# 8085-lock-schematic.net
KiCad netlist of a schematic drawn in EAGLE
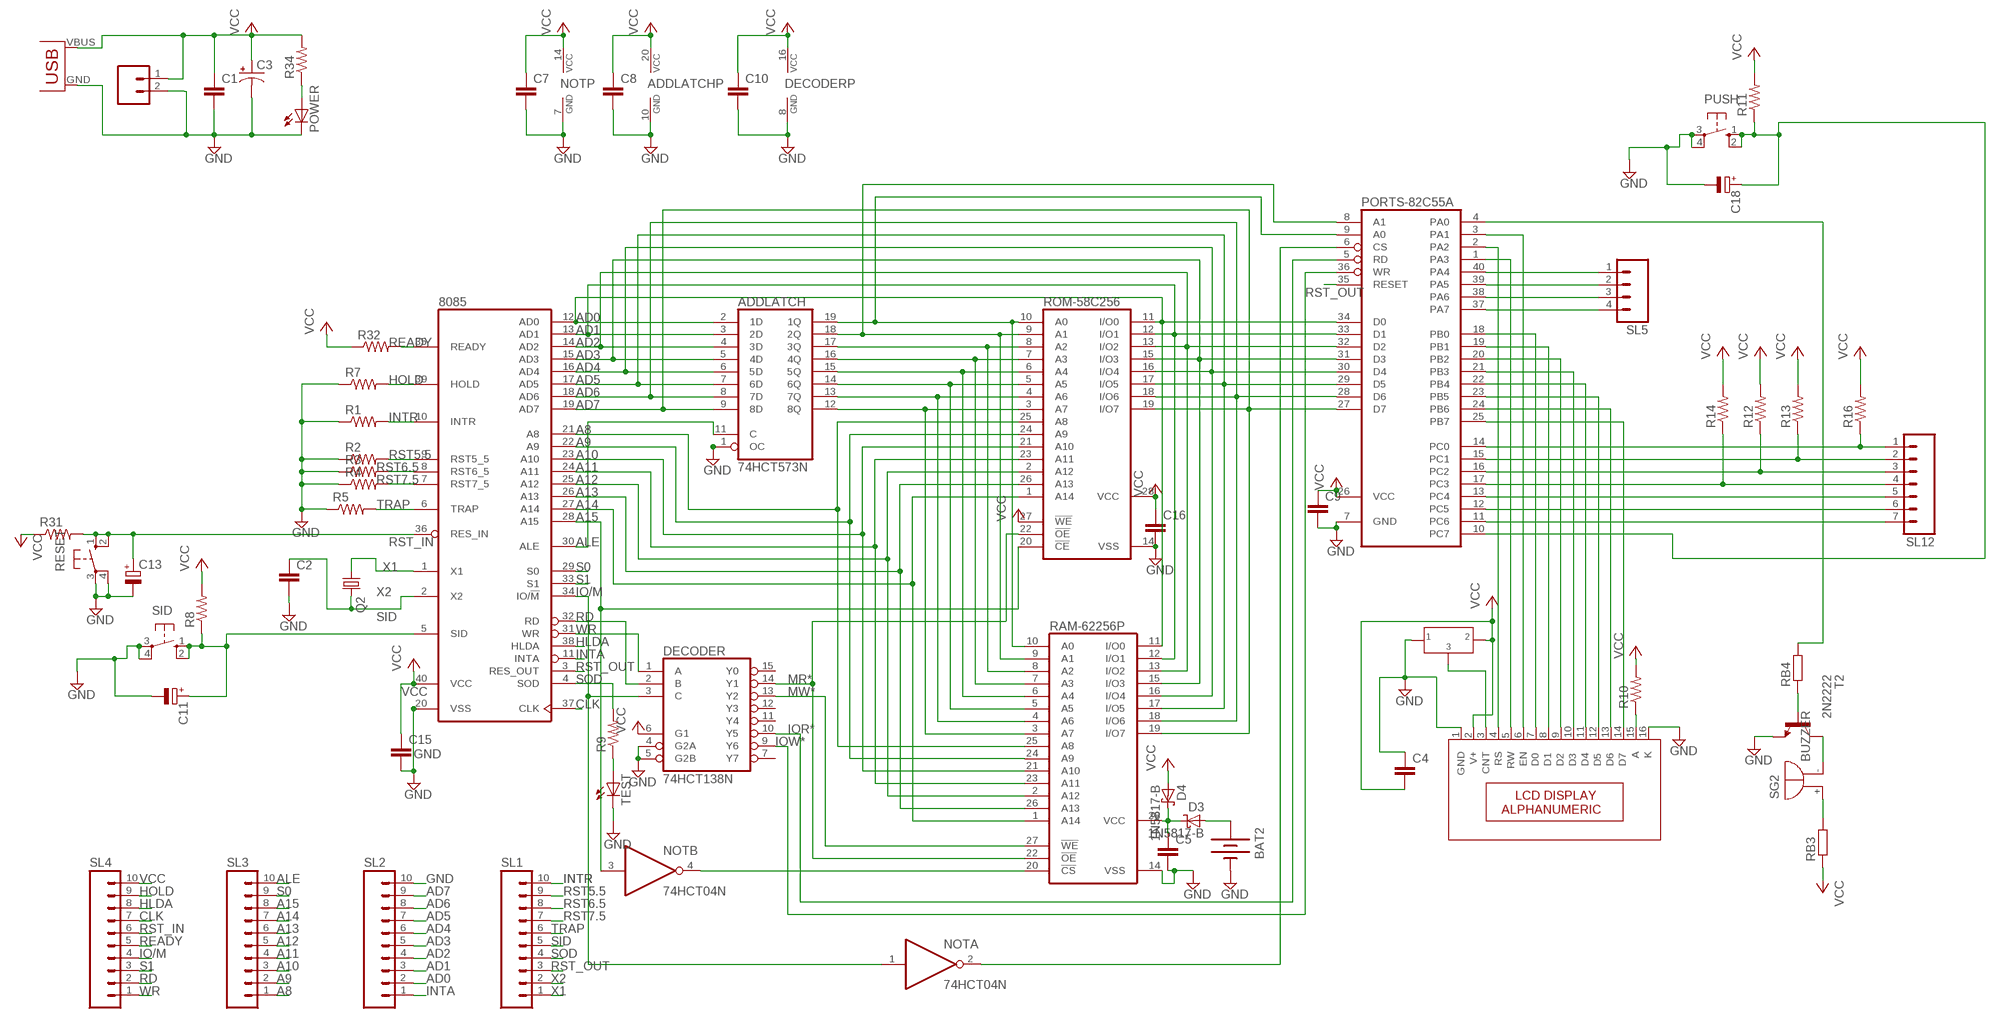
[diagram p0: schematic, sheet 1]

(export (version "E")
  (design (tool "Eeschema 10.0.6"))
  (components
    (comp (ref "8085")
      (value "8085")
      (footprint "eagle-import:DIL40")
      (libsource (lib "eagle-import") (part "8085"))
    )
    (comp (ref "ADDLATCH")
      (value "74HCT573N")
      (footprint "eagle-import:DIL20")
      (libsource (lib "eagle-import") (part "74573NHCT"))
    )
    (comp (ref "BAT2")
      (value "BATTERY20PTH")
      (footprint "eagle-import:BATTCOM_20MM_PTH")
      (libsource (lib "eagle-import") (part "BATTERY20PTH"))
    )
    (comp (ref "C1")
      (value "C-EU025-024X044")
      (footprint "eagle-import:C025-024X044")
      (libsource (lib "eagle-import") (part "C-EU025-024X044"))
    )
    (comp (ref "C2")
      (value "C-EU025-024X044")
      (footprint "eagle-import:C025-024X044")
      (libsource (lib "eagle-import") (part "C-EU025-024X044"))
    )
    (comp (ref "C3")
      (value "CPOL-USE2.5-5")
      (footprint "eagle-import:E2,5-5")
      (libsource (lib "eagle-import") (part "CPOL-USE2.5-5"))
    )
    (comp (ref "C4")
      (value "C-EU025-024X044")
      (footprint "eagle-import:C025-024X044")
      (libsource (lib "eagle-import") (part "C-EU025-024X044"))
    )
    (comp (ref "C5")
      (value "C-EU025-024X044")
      (footprint "eagle-import:C025-024X044")
      (libsource (lib "eagle-import") (part "C-EU025-024X044"))
    )
    (comp (ref "C7")
      (value "C-EU025-024X044")
      (footprint "eagle-import:C025-024X044")
      (libsource (lib "eagle-import") (part "C-EU025-024X044"))
    )
    (comp (ref "C8")
      (value "C-EU025-024X044")
      (footprint "eagle-import:C025-024X044")
      (libsource (lib "eagle-import") (part "C-EU025-024X044"))
    )
    (comp (ref "C9")
      (value "C-EU025-024X044")
      (footprint "eagle-import:C025-024X044")
      (libsource (lib "eagle-import") (part "C-EU025-024X044"))
    )
    (comp (ref "C10")
      (value "C-EU025-024X044")
      (footprint "eagle-import:C025-024X044")
      (libsource (lib "eagle-import") (part "C-EU025-024X044"))
    )
    (comp (ref "C11")
      (value "CPOL-EUE2.5-6")
      (footprint "eagle-import:E2,5-6")
      (libsource (lib "eagle-import") (part "CPOL-EUE2.5-6"))
    )
    (comp (ref "C13")
      (value "CPOL-EUE2.5-6")
      (footprint "eagle-import:E2,5-6")
      (libsource (lib "eagle-import") (part "CPOL-EUE2.5-6"))
    )
    (comp (ref "C15")
      (value "C-EU025-024X044")
      (footprint "eagle-import:C025-024X044")
      (libsource (lib "eagle-import") (part "C-EU025-024X044"))
    )
    (comp (ref "C16")
      (value "C-EU025-024X044")
      (footprint "eagle-import:C025-024X044")
      (libsource (lib "eagle-import") (part "C-EU025-024X044"))
    )
    (comp (ref "C18")
      (value "CPOL-EUE2.5-6")
      (footprint "eagle-import:E2,5-6")
      (libsource (lib "eagle-import") (part "CPOL-EUE2.5-6"))
    )
    (comp (ref "D3")
      (value "1N5817-B")
      (footprint "eagle-import:DO41-7.6")
      (libsource (lib "eagle-import") (part "1N5817-B"))
    )
    (comp (ref "D4")
      (value "1N5817-B")
      (footprint "eagle-import:DO41-7.6")
      (libsource (lib "eagle-import") (part "1N5817-B"))
    )
    (comp (ref "DECODER")
      (value "74HCT138N")
      (footprint "eagle-import:DIL16")
      (libsource (lib "eagle-import") (part "74138NHCT"))
    )
    (comp (ref "NOT")
      (value "74HCT04N")
      (footprint "eagle-import:DIL14")
      (libsource (lib "eagle-import") (part "7404NHCT"))
    )
    (comp (ref "PORTS-82C55A")
      (value "82C55A")
      (footprint "eagle-import:DIL40")
      (fields (field (name "MF") "INTERSIL") (field (name "MPN") "IP82C55AZ"))
      (libsource (lib "eagle-import") (part "82C55A"))
    )
    (comp (ref "POWER")
      (value "LED5MM")
      (footprint "eagle-import:LED5MM")
      (libsource (lib "eagle-import") (part "LED5MM"))
    )
    (comp (ref "PUSH")
      (value "10-XX")
      (footprint "eagle-import:B3F-10XX")
      (libsource (lib "eagle-import") (part "CEDTv79_10-XX"))
    )
    (comp (ref "Q2")
      (value "CRYSTALHC49US")
      (footprint "eagle-import:HC49US")
      (libsource (lib "eagle-import") (part "CRYSTALHC49US"))
    )
    (comp (ref "R1")
      (value "R-US_0207/7")
      (footprint "eagle-import:0207_7")
      (libsource (lib "eagle-import") (part "R-US_0207/7"))
    )
    (comp (ref "R2")
      (value "R-US_0207/7")
      (footprint "eagle-import:0207_7")
      (libsource (lib "eagle-import") (part "R-US_0207/7"))
    )
    (comp (ref "R3")
      (value "R-US_0207/7")
      (footprint "eagle-import:0207_7")
      (libsource (lib "eagle-import") (part "R-US_0207/7"))
    )
    (comp (ref "R4")
      (value "R-US_0207/7")
      (footprint "eagle-import:0207_7")
      (libsource (lib "eagle-import") (part "R-US_0207/7"))
    )
    (comp (ref "R5")
      (value "R-US_0207/7")
      (footprint "eagle-import:0207_7")
      (libsource (lib "eagle-import") (part "R-US_0207/7"))
    )
    (comp (ref "R6")
      (value "PRESET_LR")
      (footprint "eagle-import:PRESET_LR")
      (libsource (lib "eagle-import") (part "PRESET_LR"))
    )
    (comp (ref "R7")
      (value "R-US_0207/7")
      (footprint "eagle-import:0207_7")
      (libsource (lib "eagle-import") (part "R-US_0207/7"))
    )
    (comp (ref "R8")
      (value "R-US_0207/7")
      (footprint "eagle-import:0207_7")
      (libsource (lib "eagle-import") (part "R-US_0207/7"))
    )
    (comp (ref "R9")
      (value "R-US_0207/7")
      (footprint "eagle-import:0207_7")
      (libsource (lib "eagle-import") (part "R-US_0207/7"))
    )
    (comp (ref "R10")
      (value "R-US_0207/7")
      (footprint "eagle-import:0207_7")
      (libsource (lib "eagle-import") (part "R-US_0207/7"))
    )
    (comp (ref "R11")
      (value "R-US_0207/7")
      (footprint "eagle-import:0207_7")
      (libsource (lib "eagle-import") (part "R-US_0207/7"))
    )
    (comp (ref "R12")
      (value "R-US_0207/7")
      (footprint "eagle-import:0207_7")
      (libsource (lib "eagle-import") (part "R-US_0207/7"))
    )
    (comp (ref "R13")
      (value "R-US_0207/7")
      (footprint "eagle-import:0207_7")
      (libsource (lib "eagle-import") (part "R-US_0207/7"))
    )
    (comp (ref "R14")
      (value "R-US_0207/7")
      (footprint "eagle-import:0207_7")
      (libsource (lib "eagle-import") (part "R-US_0207/7"))
    )
    (comp (ref "R16")
      (value "R-US_0207/7")
      (footprint "eagle-import:0207_7")
      (libsource (lib "eagle-import") (part "R-US_0207/7"))
    )
    (comp (ref "R31")
      (value "R-US_0207/7")
      (footprint "eagle-import:0207_7")
      (libsource (lib "eagle-import") (part "R-US_0207/7"))
    )
    (comp (ref "R32")
      (value "R-US_0207/7")
      (footprint "eagle-import:0207_7")
      (libsource (lib "eagle-import") (part "R-US_0207/7"))
    )
    (comp (ref "R34")
      (value "R-US_0207/7")
      (footprint "eagle-import:0207_7")
      (libsource (lib "eagle-import") (part "R-US_0207/7"))
    )
    (comp (ref "RAM-62256P")
      (value "62256P")
      (footprint "eagle-import:DIL28-6")
      (libsource (lib "eagle-import") (part "62256P"))
    )
    (comp (ref "RB3")
      (value "R-EU_0204/7")
      (footprint "eagle-import:0204_7")
      (libsource (lib "eagle-import") (part "R-EU_0204/7"))
    )
    (comp (ref "RB4")
      (value "R-EU_0204/7")
      (footprint "eagle-import:0204_7")
      (libsource (lib "eagle-import") (part "R-EU_0204/7"))
    )
    (comp (ref "RESET")
      (value "10-XX")
      (footprint "eagle-import:B3F-10XX")
      (libsource (lib "eagle-import") (part "10-XX"))
    )
    (comp (ref "ROM-58C256")
      (value "58C256P")
      (footprint "eagle-import:DIL28-6")
      (fields (field (name "MPN") "HN58C256AP85E"))
      (libsource (lib "eagle-import") (part "58C256P"))
    )
    (comp (ref "SG2")
      (value "BUZZER")
      (footprint "eagle-import:F_TMB")
      (libsource (lib "eagle-import") (part "BUZZER"))
    )
    (comp (ref "SID")
      (value "10-XX")
      (footprint "eagle-import:B3F-10XX")
      (libsource (lib "eagle-import") (part "CEDTv79_10-XX"))
    )
    (comp (ref "SL1")
      (value "M10")
      (footprint "eagle-import:10P")
      (libsource (lib "eagle-import") (part "M10"))
    )
    (comp (ref "SL2")
      (value "M10")
      (footprint "eagle-import:10P")
      (libsource (lib "eagle-import") (part "M10"))
    )
    (comp (ref "SL3")
      (value "M10")
      (footprint "eagle-import:10P")
      (libsource (lib "eagle-import") (part "M10"))
    )
    (comp (ref "SL4")
      (value "M10")
      (footprint "eagle-import:10P")
      (libsource (lib "eagle-import") (part "M10"))
    )
    (comp (ref "SL5")
      (value "M04")
      (footprint "eagle-import:04P")
      (libsource (lib "eagle-import") (part "M04"))
    )
    (comp (ref "SL12")
      (value "M07")
      (footprint "eagle-import:07P")
      (libsource (lib "eagle-import") (part "M07"))
    )
    (comp (ref "T2")
      (value "2N2222")
      (footprint "eagle-import:TO18")
      (libsource (lib "eagle-import") (part "2N2222"))
    )
    (comp (ref "TEST")
      (value "LED5MM")
      (footprint "eagle-import:LED5MM")
      (libsource (lib "eagle-import") (part "LED5MM"))
    )
    (comp (ref "U$1")
      (value "M02")
      (footprint "eagle-import:02P")
      (libsource (lib "eagle-import") (part "M02"))
    )
    (comp (ref "U$2")
      (value "USB(POWER)")
      (footprint "eagle-import:USB(POWER)")
      (libsource (lib "eagle-import") (part "USB(POWER)"))
    )
    (comp (ref "U$3")
      (value "LCD-16X2")
      (footprint "eagle-import:16X2-LCD-WITH-MOUNT")
      (libsource (lib "eagle-import") (part "LCD-16X2"))
    )
  )
  (nets
    (net (code "1") (name "/A8") (class "Default")
      (node (ref "8085") (pin "21") (pinfunction "A8_21") (pintype "output"))
      (node (ref "RAM-62256P") (pin "25") (pinfunction "A8_25") (pintype "input"))
      (node (ref "ROM-58C256") (pin "25") (pinfunction "A8_25") (pintype "input"))
      (node (ref "SL3") (pin "1") (pinfunction "1_1") (pintype "passive"))
    )
    (net (code "2") (name "/A9") (class "Default")
      (node (ref "8085") (pin "22") (pinfunction "A9_22") (pintype "output"))
      (node (ref "RAM-62256P") (pin "24") (pinfunction "A9_24") (pintype "input"))
      (node (ref "ROM-58C256") (pin "24") (pinfunction "A9_24") (pintype "input"))
      (node (ref "SL3") (pin "2") (pinfunction "2_2") (pintype "passive"))
    )
    (net (code "3") (name "/A10") (class "Default")
      (node (ref "8085") (pin "23") (pinfunction "A10_23") (pintype "output"))
      (node (ref "RAM-62256P") (pin "21") (pinfunction "A10_21") (pintype "input"))
      (node (ref "ROM-58C256") (pin "21") (pinfunction "A10_21") (pintype "input"))
      (node (ref "SL3") (pin "3") (pinfunction "3_3") (pintype "passive"))
    )
    (net (code "4") (name "/A11") (class "Default")
      (node (ref "8085") (pin "24") (pinfunction "A11_24") (pintype "output"))
      (node (ref "RAM-62256P") (pin "23") (pinfunction "A11_23") (pintype "input"))
      (node (ref "ROM-58C256") (pin "23") (pinfunction "A11_23") (pintype "input"))
      (node (ref "SL3") (pin "4") (pinfunction "4_4") (pintype "passive"))
    )
    (net (code "5") (name "/A12") (class "Default")
      (node (ref "8085") (pin "25") (pinfunction "A12_25") (pintype "output"))
      (node (ref "RAM-62256P") (pin "2") (pinfunction "A12_2") (pintype "input"))
      (node (ref "ROM-58C256") (pin "2") (pinfunction "A12_2") (pintype "input"))
      (node (ref "SL3") (pin "5") (pinfunction "5_5") (pintype "passive"))
    )
    (net (code "6") (name "/A13") (class "Default")
      (node (ref "8085") (pin "26") (pinfunction "A13_26") (pintype "output"))
      (node (ref "RAM-62256P") (pin "26") (pinfunction "A13_26") (pintype "input"))
      (node (ref "ROM-58C256") (pin "26") (pinfunction "A13_26") (pintype "input"))
      (node (ref "SL3") (pin "6") (pinfunction "6_6") (pintype "passive"))
    )
    (net (code "7") (name "/A14") (class "Default")
      (node (ref "8085") (pin "27") (pinfunction "A14_27") (pintype "output"))
      (node (ref "RAM-62256P") (pin "1") (pinfunction "A14_1") (pintype "input"))
      (node (ref "ROM-58C256") (pin "1") (pinfunction "A14_1") (pintype "input"))
      (node (ref "SL3") (pin "7") (pinfunction "7_7") (pintype "passive"))
    )
    (net (code "8") (name "/A15") (class "Default")
      (node (ref "8085") (pin "28") (pinfunction "A15_28") (pintype "output"))
      (node (ref "NOT") (pin "3") (pinfunction "I_3") (pintype "input"))
      (node (ref "ROM-58C256") (pin "20") (pinfunction "~{CE}_20") (pintype "input"))
      (node (ref "SL3") (pin "8") (pinfunction "8_8") (pintype "passive"))
    )
    (net (code "9") (name "/AD0") (class "Default")
      (node (ref "8085") (pin "12") (pinfunction "AD0_12") (pintype "bidirectional"))
      (node (ref "ADDLATCH") (pin "2") (pinfunction "1D_2") (pintype "input"))
      (node (ref "PORTS-82C55A") (pin "34") (pinfunction "D0_34") (pintype "bidirectional"))
      (node (ref "RAM-62256P") (pin "11") (pinfunction "I/O0_11") (pintype "bidirectional"))
      (node (ref "ROM-58C256") (pin "11") (pinfunction "I/O0_11") (pintype "tri_state"))
      (node (ref "SL2") (pin "2") (pinfunction "2_2") (pintype "passive"))
    )
    (net (code "10") (name "/AD1") (class "Default")
      (node (ref "8085") (pin "13") (pinfunction "AD1_13") (pintype "bidirectional"))
      (node (ref "ADDLATCH") (pin "3") (pinfunction "2D_3") (pintype "input"))
      (node (ref "PORTS-82C55A") (pin "33") (pinfunction "D1_33") (pintype "bidirectional"))
      (node (ref "RAM-62256P") (pin "12") (pinfunction "I/O1_12") (pintype "bidirectional"))
      (node (ref "ROM-58C256") (pin "12") (pinfunction "I/O1_12") (pintype "tri_state"))
      (node (ref "SL2") (pin "3") (pinfunction "3_3") (pintype "passive"))
    )
    (net (code "11") (name "/AD2") (class "Default")
      (node (ref "8085") (pin "14") (pinfunction "AD2_14") (pintype "bidirectional"))
      (node (ref "ADDLATCH") (pin "4") (pinfunction "3D_4") (pintype "input"))
      (node (ref "PORTS-82C55A") (pin "32") (pinfunction "D2_32") (pintype "bidirectional"))
      (node (ref "RAM-62256P") (pin "13") (pinfunction "I/O2_13") (pintype "bidirectional"))
      (node (ref "ROM-58C256") (pin "13") (pinfunction "I/O2_13") (pintype "tri_state"))
      (node (ref "SL2") (pin "4") (pinfunction "4_4") (pintype "passive"))
    )
    (net (code "12") (name "/AD3") (class "Default")
      (node (ref "8085") (pin "15") (pinfunction "AD3_15") (pintype "bidirectional"))
      (node (ref "ADDLATCH") (pin "5") (pinfunction "4D_5") (pintype "input"))
      (node (ref "PORTS-82C55A") (pin "31") (pinfunction "D3_31") (pintype "bidirectional"))
      (node (ref "RAM-62256P") (pin "15") (pinfunction "I/O3_15") (pintype "bidirectional"))
      (node (ref "ROM-58C256") (pin "15") (pinfunction "I/O3_15") (pintype "tri_state"))
      (node (ref "SL2") (pin "5") (pinfunction "5_5") (pintype "passive"))
    )
    (net (code "13") (name "/AD4") (class "Default")
      (node (ref "8085") (pin "16") (pinfunction "AD4_16") (pintype "bidirectional"))
      (node (ref "ADDLATCH") (pin "6") (pinfunction "5D_6") (pintype "input"))
      (node (ref "PORTS-82C55A") (pin "30") (pinfunction "D4_30") (pintype "bidirectional"))
      (node (ref "RAM-62256P") (pin "16") (pinfunction "I/O4_16") (pintype "bidirectional"))
      (node (ref "ROM-58C256") (pin "16") (pinfunction "I/O4_16") (pintype "tri_state"))
      (node (ref "SL2") (pin "6") (pinfunction "6_6") (pintype "passive"))
    )
    (net (code "14") (name "/AD5") (class "Default")
      (node (ref "8085") (pin "17") (pinfunction "AD5_17") (pintype "bidirectional"))
      (node (ref "ADDLATCH") (pin "7") (pinfunction "6D_7") (pintype "input"))
      (node (ref "PORTS-82C55A") (pin "29") (pinfunction "D5_29") (pintype "bidirectional"))
      (node (ref "RAM-62256P") (pin "17") (pinfunction "I/O5_17") (pintype "bidirectional"))
      (node (ref "ROM-58C256") (pin "17") (pinfunction "I/O5_17") (pintype "tri_state"))
      (node (ref "SL2") (pin "7") (pinfunction "7_7") (pintype "passive"))
    )
    (net (code "15") (name "/AD6") (class "Default")
      (node (ref "8085") (pin "18") (pinfunction "AD6_18") (pintype "bidirectional"))
      (node (ref "ADDLATCH") (pin "8") (pinfunction "7D_8") (pintype "input"))
      (node (ref "PORTS-82C55A") (pin "28") (pinfunction "D6_28") (pintype "bidirectional"))
      (node (ref "RAM-62256P") (pin "18") (pinfunction "I/O6_18") (pintype "bidirectional"))
      (node (ref "ROM-58C256") (pin "18") (pinfunction "I/O6_18") (pintype "tri_state"))
      (node (ref "SL2") (pin "8") (pinfunction "8_8") (pintype "passive"))
    )
    (net (code "16") (name "/AD7") (class "Default")
      (node (ref "8085") (pin "19") (pinfunction "AD7_19") (pintype "bidirectional"))
      (node (ref "ADDLATCH") (pin "9") (pinfunction "8D_9") (pintype "input"))
      (node (ref "PORTS-82C55A") (pin "27") (pinfunction "D7_27") (pintype "bidirectional"))
      (node (ref "RAM-62256P") (pin "19") (pinfunction "I/O7_19") (pintype "bidirectional"))
      (node (ref "ROM-58C256") (pin "19") (pinfunction "I/O7_19") (pintype "tri_state"))
      (node (ref "SL2") (pin "9") (pinfunction "9_9") (pintype "passive"))
    )
    (net (code "17") (name "/ALE") (class "Default")
      (node (ref "8085") (pin "30") (pinfunction "ALE_30") (pintype "output"))
      (node (ref "ADDLATCH") (pin "11") (pinfunction "C_11") (pintype "input"))
      (node (ref "SL3") (pin "10") (pinfunction "10_10") (pintype "passive"))
    )
    (net (code "18") (name "/CLK") (class "Default")
      (node (ref "8085") (pin "37") (pinfunction "CLK_37") (pintype "output"))
      (node (ref "SL4") (pin "7") (pinfunction "7_7") (pintype "passive"))
    )
    (net (code "19") (name "/HLDA") (class "Default")
      (node (ref "8085") (pin "38") (pinfunction "HLDA_38") (pintype "output"))
      (node (ref "SL4") (pin "8") (pinfunction "8_8") (pintype "passive"))
    )
    (net (code "20") (name "/HOLD") (class "Default")
      (node (ref "8085") (pin "39") (pinfunction "HOLD_39") (pintype "input"))
      (node (ref "R7") (pin "2") (pinfunction "2_2") (pintype "passive"))
      (node (ref "SL4") (pin "9") (pinfunction "9_9") (pintype "passive"))
    )
    (net (code "21") (name "/INTA") (class "Default")
      (node (ref "8085") (pin "11") (pinfunction "INTA_11") (pintype "output"))
      (node (ref "SL2") (pin "1") (pinfunction "1_1") (pintype "passive"))
    )
    (net (code "22") (name "/INTR") (class "Default")
      (node (ref "8085") (pin "10") (pinfunction "INTR_10") (pintype "input"))
      (node (ref "R1") (pin "2") (pinfunction "2_2") (pintype "passive"))
      (node (ref "SL1") (pin "10") (pinfunction "10_10") (pintype "passive"))
    )
    (net (code "23") (name "/IOR*") (class "Default")
      (node (ref "DECODER") (pin "10") (pinfunction "Y5_10") (pintype "output"))
      (node (ref "PORTS-82C55A") (pin "5") (pinfunction "RD_5") (pintype "input"))
    )
    (net (code "24") (name "/IOW*") (class "Default")
      (node (ref "DECODER") (pin "9") (pinfunction "Y6_9") (pintype "output"))
      (node (ref "PORTS-82C55A") (pin "36") (pinfunction "WR_36") (pintype "input"))
    )
    (net (code "25") (name "/IO{slash}M") (class "Default")
      (node (ref "8085") (pin "34") (pinfunction "IO/~{M}_34") (pintype "output"))
      (node (ref "DECODER") (pin "3") (pinfunction "C_3") (pintype "input"))
      (node (ref "NOT") (pin "1") (pinfunction "I_1") (pintype "input"))
      (node (ref "SL4") (pin "4") (pinfunction "4_4") (pintype "passive"))
    )
    (net (code "26") (name "/MR*") (class "Default")
      (node (ref "DECODER") (pin "14") (pinfunction "Y1_14") (pintype "output"))
      (node (ref "RAM-62256P") (pin "22") (pinfunction "~{OE}_22") (pintype "input"))
      (node (ref "ROM-58C256") (pin "22") (pinfunction "~{OE}_22") (pintype "input"))
    )
    (net (code "27") (name "/MW*") (class "Default")
      (node (ref "DECODER") (pin "13") (pinfunction "Y2_13") (pintype "output"))
      (node (ref "RAM-62256P") (pin "27") (pinfunction "~{WE}_27") (pintype "input"))
    )
    (net (code "28") (name "/RD") (class "Default")
      (node (ref "8085") (pin "32") (pinfunction "RD_32") (pintype "output"))
      (node (ref "DECODER") (pin "2") (pinfunction "B_2") (pintype "input"))
      (node (ref "SL4") (pin "2") (pinfunction "2_2") (pintype "passive"))
    )
    (net (code "29") (name "/READY") (class "Default")
      (node (ref "8085") (pin "35") (pinfunction "READY_35") (pintype "input"))
      (node (ref "R32") (pin "2") (pinfunction "2_2") (pintype "passive"))
      (node (ref "SL4") (pin "5") (pinfunction "5_5") (pintype "passive"))
    )
    (net (code "30") (name "/RST5.5") (class "Default")
      (node (ref "8085") (pin "9") (pinfunction "RST5_5_9") (pintype "input"))
      (node (ref "R2") (pin "2") (pinfunction "2_2") (pintype "passive"))
      (node (ref "SL1") (pin "9") (pinfunction "9_9") (pintype "passive"))
    )
    (net (code "31") (name "/RST6.5") (class "Default")
      (node (ref "8085") (pin "8") (pinfunction "RST6_5_8") (pintype "input"))
      (node (ref "R3") (pin "2") (pinfunction "2_2") (pintype "passive"))
      (node (ref "SL1") (pin "8") (pinfunction "8_8") (pintype "passive"))
    )
    (net (code "32") (name "/RST7.5") (class "Default")
      (node (ref "8085") (pin "7") (pinfunction "RST7_5_7") (pintype "input"))
      (node (ref "R4") (pin "2") (pinfunction "2_2") (pintype "passive"))
      (node (ref "SL1") (pin "7") (pinfunction "7_7") (pintype "passive"))
    )
    (net (code "33") (name "/RST_IN") (class "Default")
      (node (ref "8085") (pin "36") (pinfunction "RES_IN_36") (pintype "input"))
      (node (ref "C13") (pin "+") (pinfunction "+_+") (pintype "passive"))
      (node (ref "R31") (pin "2") (pinfunction "2_2") (pintype "passive"))
      (node (ref "RESET") (pin "1") (pinfunction "S_1") (pintype "passive"))
      (node (ref "RESET") (pin "2") (pinfunction "S1_2") (pintype "passive"))
      (node (ref "SL4") (pin "6") (pinfunction "6_6") (pintype "passive"))
    )
    (net (code "34") (name "/RST_OUT") (class "Default")
      (node (ref "8085") (pin "3") (pinfunction "RES_OUT_3") (pintype "output"))
      (node (ref "PORTS-82C55A") (pin "35") (pinfunction "RESET_35") (pintype "input"))
      (node (ref "SL1") (pin "3") (pinfunction "3_3") (pintype "passive"))
    )
    (net (code "35") (name "/S0") (class "Default")
      (node (ref "8085") (pin "29") (pinfunction "S0_29") (pintype "output"))
      (node (ref "SL3") (pin "9") (pinfunction "9_9") (pintype "passive"))
    )
    (net (code "36") (name "/S1") (class "Default")
      (node (ref "8085") (pin "33") (pinfunction "S1_33") (pintype "output"))
      (node (ref "SL4") (pin "3") (pinfunction "3_3") (pintype "passive"))
    )
    (net (code "37") (name "/SID") (class "Default")
      (node (ref "8085") (pin "5") (pinfunction "SID_5") (pintype "input"))
      (node (ref "C11") (pin "+") (pinfunction "+_+") (pintype "passive"))
      (node (ref "R8") (pin "1") (pinfunction "1_1") (pintype "passive"))
      (node (ref "SID") (pin "1") (pinfunction "S_1") (pintype "passive"))
      (node (ref "SID") (pin "2") (pinfunction "S1_2") (pintype "passive"))
      (node (ref "SL1") (pin "5") (pinfunction "5_5") (pintype "passive"))
    )
    (net (code "38") (name "/SOD") (class "Default")
      (node (ref "8085") (pin "4") (pinfunction "SOD_4") (pintype "output"))
      (node (ref "R9") (pin "2") (pinfunction "2_2") (pintype "passive"))
      (node (ref "SL1") (pin "4") (pinfunction "4_4") (pintype "passive"))
    )
    (net (code "39") (name "/TRAP") (class "Default")
      (node (ref "8085") (pin "6") (pinfunction "TRAP_6") (pintype "input"))
      (node (ref "R5") (pin "2") (pinfunction "2_2") (pintype "passive"))
      (node (ref "SL1") (pin "6") (pinfunction "6_6") (pintype "passive"))
    )
    (net (code "40") (name "/WR") (class "Default")
      (node (ref "8085") (pin "31") (pinfunction "WR_31") (pintype "output"))
      (node (ref "DECODER") (pin "1") (pinfunction "A_1") (pintype "input"))
      (node (ref "SL4") (pin "1") (pinfunction "1_1") (pintype "passive"))
    )
    (net (code "41") (name "/X1") (class "Default")
      (node (ref "8085") (pin "1") (pinfunction "X1_1") (pintype "input"))
      (node (ref "Q2") (pin "1") (pinfunction "1_1") (pintype "passive"))
      (node (ref "SL1") (pin "1") (pinfunction "1_1") (pintype "passive"))
    )
    (net (code "42") (name "/X2") (class "Default")
      (node (ref "8085") (pin "2") (pinfunction "X2_2") (pintype "input"))
      (node (ref "C2") (pin "1") (pinfunction "1_1") (pintype "passive"))
      (node (ref "Q2") (pin "2") (pinfunction "2_2") (pintype "passive"))
      (node (ref "SL1") (pin "2") (pinfunction "2_2") (pintype "passive"))
    )
    (net (code "43") (name "GND") (class "Default")
      (node (ref "8085") (pin "20") (pinfunction "VSS_20") (pintype "power_in"))
      (node (ref "ADDLATCH") (pin "1") (pinfunction "OC_1") (pintype "input"))
      (node (ref "ADDLATCH") (pin "10") (pinfunction "GND_10") (pintype "power_in"))
      (node (ref "BAT2") (pin "2") (pinfunction "-_2") (pintype "power_in"))
      (node (ref "C1") (pin "2") (pinfunction "2_2") (pintype "passive"))
      (node (ref "C10") (pin "2") (pinfunction "2_2") (pintype "passive"))
      (node (ref "C11") (pin "-") (pinfunction "-_-") (pintype "passive"))
      (node (ref "C13") (pin "-") (pinfunction "-_-") (pintype "passive"))
      (node (ref "C15") (pin "2") (pinfunction "2_2") (pintype "passive"))
      (node (ref "C16") (pin "2") (pinfunction "2_2") (pintype "passive"))
      (node (ref "C18") (pin "-") (pinfunction "-_-") (pintype "passive"))
      (node (ref "C2") (pin "2") (pinfunction "2_2") (pintype "passive"))
      (node (ref "C3") (pin "-") (pinfunction "-_-") (pintype "passive"))
      (node (ref "C4") (pin "1") (pinfunction "1_1") (pintype "passive"))
      (node (ref "C5") (pin "2") (pinfunction "2_2") (pintype "passive"))
      (node (ref "C7") (pin "2") (pinfunction "2_2") (pintype "passive"))
      (node (ref "C8") (pin "2") (pinfunction "2_2") (pintype "passive"))
      (node (ref "C9") (pin "2") (pinfunction "2_2") (pintype "passive"))
      (node (ref "DECODER") (pin "4") (pinfunction "G2A_4") (pintype "input"))
      (node (ref "DECODER") (pin "5") (pinfunction "G2B_5") (pintype "input"))
      (node (ref "DECODER") (pin "8") (pinfunction "GND_8") (pintype "power_in"))
      (node (ref "NOT") (pin "7") (pinfunction "GND_7") (pintype "power_in"))
      (node (ref "PORTS-82C55A") (pin "7") (pinfunction "GND_7") (pintype "power_in"))
      (node (ref "POWER") (pin "K") (pinfunction "C_K") (pintype "passive"))
      (node (ref "PUSH") (pin "3") (pinfunction "P_3") (pintype "passive"))
      (node (ref "PUSH") (pin "4") (pinfunction "P1_4") (pintype "passive"))
      (node (ref "R1") (pin "1") (pinfunction "1_1") (pintype "passive"))
      (node (ref "R2") (pin "1") (pinfunction "1_1") (pintype "passive"))
      (node (ref "R3") (pin "1") (pinfunction "1_1") (pintype "passive"))
      (node (ref "R4") (pin "1") (pinfunction "1_1") (pintype "passive"))
      (node (ref "R5") (pin "1") (pinfunction "1_1") (pintype "passive"))
      (node (ref "R6") (pin "P$1") (pinfunction "1_P$1") (pintype "passive"))
      (node (ref "R7") (pin "1") (pinfunction "1_1") (pintype "passive"))
      (node (ref "RAM-62256P") (pin "14") (pinfunction "VSS_14") (pintype "power_in"))
      (node (ref "RESET") (pin "3") (pinfunction "P_3") (pintype "passive"))
      (node (ref "RESET") (pin "4") (pinfunction "P1_4") (pintype "passive"))
      (node (ref "ROM-58C256") (pin "14") (pinfunction "VSS_14") (pintype "power_in"))
      (node (ref "SID") (pin "3") (pinfunction "P_3") (pintype "passive"))
      (node (ref "SID") (pin "4") (pinfunction "P1_4") (pintype "passive"))
      (node (ref "SL2") (pin "10") (pinfunction "10_10") (pintype "passive"))
      (node (ref "T2") (pin "1") (pinfunction "E_1") (pintype "passive"))
      (node (ref "TEST") (pin "K") (pinfunction "C_K") (pintype "passive"))
      (node (ref "U$1") (pin "2") (pinfunction "2_2") (pintype "passive"))
      (node (ref "U$2") (pin "GND") (pinfunction "GND_GND") (pintype "power_in"))
      (node (ref "U$3") (pin "1") (pinfunction "GND_1") (pintype "power_in"))
      (node (ref "U$3") (pin "16") (pinfunction "K_16") (pintype "bidirectional"))
    )
    (net (code "44") (name "Net-(ADDLATCHA-1Q)") (class "Default")
      (node (ref "ADDLATCH") (pin "19") (pinfunction "1Q_19") (pintype "tri_state"))
      (node (ref "PORTS-82C55A") (pin "9") (pinfunction "A0_9") (pintype "input"))
      (node (ref "RAM-62256P") (pin "10") (pinfunction "A0_10") (pintype "input"))
      (node (ref "ROM-58C256") (pin "10") (pinfunction "A0_10") (pintype "input"))
    )
    (net (code "45") (name "Net-(ADDLATCHA-2Q)") (class "Default")
      (node (ref "ADDLATCH") (pin "18") (pinfunction "2Q_18") (pintype "tri_state"))
      (node (ref "PORTS-82C55A") (pin "8") (pinfunction "A1_8") (pintype "input"))
      (node (ref "RAM-62256P") (pin "9") (pinfunction "A1_9") (pintype "input"))
      (node (ref "ROM-58C256") (pin "9") (pinfunction "A1_9") (pintype "input"))
    )
    (net (code "46") (name "Net-(ADDLATCHA-3Q)") (class "Default")
      (node (ref "ADDLATCH") (pin "17") (pinfunction "3Q_17") (pintype "tri_state"))
      (node (ref "RAM-62256P") (pin "8") (pinfunction "A2_8") (pintype "input"))
      (node (ref "ROM-58C256") (pin "8") (pinfunction "A2_8") (pintype "input"))
    )
    (net (code "47") (name "Net-(ADDLATCHA-4Q)") (class "Default")
      (node (ref "ADDLATCH") (pin "16") (pinfunction "4Q_16") (pintype "tri_state"))
      (node (ref "RAM-62256P") (pin "7") (pinfunction "A3_7") (pintype "input"))
      (node (ref "ROM-58C256") (pin "7") (pinfunction "A3_7") (pintype "input"))
    )
    (net (code "48") (name "Net-(ADDLATCHA-5Q)") (class "Default")
      (node (ref "ADDLATCH") (pin "15") (pinfunction "5Q_15") (pintype "tri_state"))
      (node (ref "RAM-62256P") (pin "6") (pinfunction "A4_6") (pintype "input"))
      (node (ref "ROM-58C256") (pin "6") (pinfunction "A4_6") (pintype "input"))
    )
    (net (code "49") (name "Net-(ADDLATCHA-6Q)") (class "Default")
      (node (ref "ADDLATCH") (pin "14") (pinfunction "6Q_14") (pintype "tri_state"))
      (node (ref "RAM-62256P") (pin "5") (pinfunction "A5_5") (pintype "input"))
      (node (ref "ROM-58C256") (pin "5") (pinfunction "A5_5") (pintype "input"))
    )
    (net (code "50") (name "Net-(ADDLATCHA-7Q)") (class "Default")
      (node (ref "ADDLATCH") (pin "13") (pinfunction "7Q_13") (pintype "tri_state"))
      (node (ref "RAM-62256P") (pin "4") (pinfunction "A6_4") (pintype "input"))
      (node (ref "ROM-58C256") (pin "4") (pinfunction "A6_4") (pintype "input"))
    )
    (net (code "51") (name "Net-(ADDLATCHA-8Q)") (class "Default")
      (node (ref "ADDLATCH") (pin "12") (pinfunction "8Q_12") (pintype "tri_state"))
      (node (ref "RAM-62256P") (pin "3") (pinfunction "A7_3") (pintype "input"))
      (node (ref "ROM-58C256") (pin "3") (pinfunction "A7_3") (pintype "input"))
    )
    (net (code "52") (name "Net-(BAT2-+)") (class "Default")
      (node (ref "BAT2") (pin "1") (pinfunction "+_1") (pintype "power_in"))
      (node (ref "D3") (pin "A") (pinfunction "A_A") (pintype "passive"))
    )
    (net (code "53") (name "Net-(NOTA-O)") (class "Default")
      (node (ref "NOT") (pin "2") (pinfunction "O_2") (pintype "output"))
      (node (ref "PORTS-82C55A") (pin "6") (pinfunction "CS_6") (pintype "input"))
    )
    (net (code "54") (name "Net-(NOTB-O)") (class "Default")
      (node (ref "NOT") (pin "4") (pinfunction "O_4") (pintype "output"))
      (node (ref "RAM-62256P") (pin "20") (pinfunction "~{CS}_20") (pintype "input"))
    )
    (net (code "55") (name "Net-(PORTS-82C55A-PA0)") (class "Default")
      (node (ref "PORTS-82C55A") (pin "4") (pinfunction "PA0_4") (pintype "bidirectional"))
      (node (ref "RB4") (pin "2") (pinfunction "2_2") (pintype "passive"))
    )
    (net (code "56") (name "Net-(PORTS-82C55A-PA1)") (class "Default")
      (node (ref "PORTS-82C55A") (pin "3") (pinfunction "PA1_3") (pintype "bidirectional"))
      (node (ref "U$3") (pin "6") (pinfunction "EN_6") (pintype "bidirectional"))
    )
    (net (code "57") (name "Net-(PORTS-82C55A-PA2)") (class "Default")
      (node (ref "PORTS-82C55A") (pin "2") (pinfunction "PA2_2") (pintype "bidirectional"))
      (node (ref "U$3") (pin "4") (pinfunction "RS_4") (pintype "bidirectional"))
    )
    (net (code "58") (name "Net-(PORTS-82C55A-PA3)") (class "Default")
      (node (ref "PORTS-82C55A") (pin "1") (pinfunction "PA3_1") (pintype "bidirectional"))
      (node (ref "U$3") (pin "5") (pinfunction "RW_5") (pintype "bidirectional"))
    )
    (net (code "59") (name "Net-(PORTS-82C55A-PA4)") (class "Default")
      (node (ref "PORTS-82C55A") (pin "40") (pinfunction "PA4_40") (pintype "bidirectional"))
      (node (ref "SL5") (pin "1") (pinfunction "1_1") (pintype "passive"))
    )
    (net (code "60") (name "Net-(PORTS-82C55A-PA5)") (class "Default")
      (node (ref "PORTS-82C55A") (pin "39") (pinfunction "PA5_39") (pintype "bidirectional"))
      (node (ref "SL5") (pin "2") (pinfunction "2_2") (pintype "passive"))
    )
    (net (code "61") (name "Net-(PORTS-82C55A-PA6)") (class "Default")
      (node (ref "PORTS-82C55A") (pin "38") (pinfunction "PA6_38") (pintype "bidirectional"))
      (node (ref "SL5") (pin "3") (pinfunction "3_3") (pintype "passive"))
    )
    (net (code "62") (name "Net-(PORTS-82C55A-PA7)") (class "Default")
      (node (ref "PORTS-82C55A") (pin "37") (pinfunction "PA7_37") (pintype "bidirectional"))
      (node (ref "SL5") (pin "4") (pinfunction "4_4") (pintype "passive"))
    )
    (net (code "63") (name "Net-(PORTS-82C55A-PB0)") (class "Default")
      (node (ref "PORTS-82C55A") (pin "18") (pinfunction "PB0_18") (pintype "bidirectional"))
      (node (ref "U$3") (pin "7") (pinfunction "D0_7") (pintype "bidirectional"))
    )
    (net (code "64") (name "Net-(PORTS-82C55A-PB1)") (class "Default")
      (node (ref "PORTS-82C55A") (pin "19") (pinfunction "PB1_19") (pintype "bidirectional"))
      (node (ref "U$3") (pin "8") (pinfunction "D1_8") (pintype "bidirectional"))
    )
    (net (code "65") (name "Net-(PORTS-82C55A-PB2)") (class "Default")
      (node (ref "PORTS-82C55A") (pin "20") (pinfunction "PB2_20") (pintype "bidirectional"))
      (node (ref "U$3") (pin "9") (pinfunction "D2_9") (pintype "bidirectional"))
    )
    (net (code "66") (name "Net-(PORTS-82C55A-PB3)") (class "Default")
      (node (ref "PORTS-82C55A") (pin "21") (pinfunction "PB3_21") (pintype "bidirectional"))
      (node (ref "U$3") (pin "10") (pinfunction "D3_10") (pintype "bidirectional"))
    )
    (net (code "67") (name "Net-(PORTS-82C55A-PB4)") (class "Default")
      (node (ref "PORTS-82C55A") (pin "22") (pinfunction "PB4_22") (pintype "bidirectional"))
      (node (ref "U$3") (pin "11") (pinfunction "D4_11") (pintype "bidirectional"))
    )
    (net (code "68") (name "Net-(PORTS-82C55A-PB5)") (class "Default")
      (node (ref "PORTS-82C55A") (pin "23") (pinfunction "PB5_23") (pintype "bidirectional"))
      (node (ref "U$3") (pin "12") (pinfunction "D5_12") (pintype "bidirectional"))
    )
    (net (code "69") (name "Net-(PORTS-82C55A-PB6)") (class "Default")
      (node (ref "PORTS-82C55A") (pin "24") (pinfunction "PB6_24") (pintype "bidirectional"))
      (node (ref "U$3") (pin "13") (pinfunction "D6_13") (pintype "bidirectional"))
    )
    (net (code "70") (name "Net-(PORTS-82C55A-PB7)") (class "Default")
      (node (ref "PORTS-82C55A") (pin "25") (pinfunction "PB7_25") (pintype "bidirectional"))
      (node (ref "U$3") (pin "14") (pinfunction "D7_14") (pintype "bidirectional"))
    )
    (net (code "71") (name "Net-(PORTS-82C55A-PC0)") (class "Default")
      (node (ref "PORTS-82C55A") (pin "14") (pinfunction "PC0_14") (pintype "bidirectional"))
      (node (ref "R16") (pin "1") (pinfunction "1_1") (pintype "passive"))
      (node (ref "SL12") (pin "1") (pinfunction "1_1") (pintype "passive"))
    )
    (net (code "72") (name "Net-(PORTS-82C55A-PC1)") (class "Default")
      (node (ref "PORTS-82C55A") (pin "15") (pinfunction "PC1_15") (pintype "bidirectional"))
      (node (ref "R13") (pin "1") (pinfunction "1_1") (pintype "passive"))
      (node (ref "SL12") (pin "2") (pinfunction "2_2") (pintype "passive"))
    )
    (net (code "73") (name "Net-(PORTS-82C55A-PC2)") (class "Default")
      (node (ref "PORTS-82C55A") (pin "16") (pinfunction "PC2_16") (pintype "bidirectional"))
      (node (ref "R12") (pin "1") (pinfunction "1_1") (pintype "passive"))
      (node (ref "SL12") (pin "3") (pinfunction "3_3") (pintype "passive"))
    )
    (net (code "74") (name "Net-(PORTS-82C55A-PC3)") (class "Default")
      (node (ref "PORTS-82C55A") (pin "17") (pinfunction "PC3_17") (pintype "bidirectional"))
      (node (ref "R14") (pin "1") (pinfunction "1_1") (pintype "passive"))
      (node (ref "SL12") (pin "4") (pinfunction "4_4") (pintype "passive"))
    )
    (net (code "75") (name "Net-(PORTS-82C55A-PC4)") (class "Default")
      (node (ref "PORTS-82C55A") (pin "13") (pinfunction "PC4_13") (pintype "bidirectional"))
      (node (ref "SL12") (pin "5") (pinfunction "5_5") (pintype "passive"))
    )
    (net (code "76") (name "Net-(PORTS-82C55A-PC5)") (class "Default")
      (node (ref "PORTS-82C55A") (pin "12") (pinfunction "PC5_12") (pintype "bidirectional"))
      (node (ref "SL12") (pin "6") (pinfunction "6_6") (pintype "passive"))
    )
    (net (code "77") (name "Net-(PORTS-82C55A-PC6)") (class "Default")
      (node (ref "PORTS-82C55A") (pin "11") (pinfunction "PC6_11") (pintype "bidirectional"))
      (node (ref "SL12") (pin "7") (pinfunction "7_7") (pintype "passive"))
    )
    (net (code "78") (name "Net-(PORTS-82C55A-PC7)") (class "Default")
      (node (ref "C18") (pin "+") (pinfunction "+_+") (pintype "passive"))
      (node (ref "PORTS-82C55A") (pin "10") (pinfunction "PC7_10") (pintype "bidirectional"))
      (node (ref "PUSH") (pin "1") (pinfunction "S_1") (pintype "passive"))
      (node (ref "PUSH") (pin "2") (pinfunction "S1_2") (pintype "passive"))
      (node (ref "R11") (pin "1") (pinfunction "1_1") (pintype "passive"))
    )
    (net (code "79") (name "Net-(POWER-PadA)") (class "Default")
      (node (ref "POWER") (pin "A") (pinfunction "A_A") (pintype "passive"))
      (node (ref "R34") (pin "1") (pinfunction "1_1") (pintype "passive"))
    )
    (net (code "80") (name "Net-(R6-3)") (class "Default")
      (node (ref "R6") (pin "P$3") (pinfunction "3_P$3") (pintype "passive"))
      (node (ref "U$3") (pin "3") (pinfunction "CNT_3") (pintype "bidirectional"))
    )
    (net (code "81") (name "Net-(R9-Pad1)") (class "Default")
      (node (ref "R9") (pin "1") (pinfunction "1_1") (pintype "passive"))
      (node (ref "TEST") (pin "A") (pinfunction "A_A") (pintype "passive"))
    )
    (net (code "82") (name "Net-(RAM-62256P-VCC)") (class "Default")
      (node (ref "C5") (pin "1") (pinfunction "1_1") (pintype "passive"))
      (node (ref "D3") (pin "C") (pinfunction "C_C") (pintype "passive"))
      (node (ref "D4") (pin "C") (pinfunction "C_C") (pintype "passive"))
      (node (ref "RAM-62256P") (pin "28") (pinfunction "VCC_28") (pintype "power_in"))
    )
    (net (code "83") (name "Net-(RB3-Pad2)") (class "Default")
      (node (ref "RB3") (pin "2") (pinfunction "2_2") (pintype "passive"))
      (node (ref "SG2") (pin "+") (pinfunction "+_+") (pintype "passive"))
    )
    (net (code "84") (name "Net-(T2-B)") (class "Default")
      (node (ref "RB4") (pin "1") (pinfunction "1_1") (pintype "passive"))
      (node (ref "T2") (pin "2") (pinfunction "B_2") (pintype "passive"))
    )
    (net (code "85") (name "Net-(T2-C)") (class "Default")
      (node (ref "SG2") (pin "-") (pinfunction "-_-") (pintype "passive"))
      (node (ref "T2") (pin "3") (pinfunction "C_3") (pintype "passive"))
    )
    (net (code "86") (name "Net-(U$3-A)") (class "Default")
      (node (ref "R10") (pin "1") (pinfunction "1_1") (pintype "passive"))
      (node (ref "U$3") (pin "15") (pinfunction "A_15") (pintype "bidirectional"))
    )
    (net (code "87") (name "VCC") (class "Default")
      (node (ref "8085") (pin "40") (pinfunction "VCC_40") (pintype "power_in"))
      (node (ref "ADDLATCH") (pin "20") (pinfunction "VCC_20") (pintype "power_in"))
      (node (ref "C1") (pin "1") (pinfunction "1_1") (pintype "passive"))
      (node (ref "C10") (pin "1") (pinfunction "1_1") (pintype "passive"))
      (node (ref "C15") (pin "1") (pinfunction "1_1") (pintype "passive"))
      (node (ref "C16") (pin "1") (pinfunction "1_1") (pintype "passive"))
      (node (ref "C3") (pin "+") (pinfunction "+_+") (pintype "passive"))
      (node (ref "C4") (pin "2") (pinfunction "2_2") (pintype "passive"))
      (node (ref "C7") (pin "1") (pinfunction "1_1") (pintype "passive"))
      (node (ref "C8") (pin "1") (pinfunction "1_1") (pintype "passive"))
      (node (ref "C9") (pin "1") (pinfunction "1_1") (pintype "passive"))
      (node (ref "D4") (pin "A") (pinfunction "A_A") (pintype "passive"))
      (node (ref "DECODER") (pin "16") (pinfunction "VCC_16") (pintype "power_in"))
      (node (ref "DECODER") (pin "6") (pinfunction "G1_6") (pintype "input"))
      (node (ref "NOT") (pin "14") (pinfunction "VCC_14") (pintype "power_in"))
      (node (ref "PORTS-82C55A") (pin "26") (pinfunction "VCC_26") (pintype "power_in"))
      (node (ref "R10") (pin "2") (pinfunction "2_2") (pintype "passive"))
      (node (ref "R11") (pin "2") (pinfunction "2_2") (pintype "passive"))
      (node (ref "R12") (pin "2") (pinfunction "2_2") (pintype "passive"))
      (node (ref "R13") (pin "2") (pinfunction "2_2") (pintype "passive"))
      (node (ref "R14") (pin "2") (pinfunction "2_2") (pintype "passive"))
      (node (ref "R16") (pin "2") (pinfunction "2_2") (pintype "passive"))
      (node (ref "R31") (pin "1") (pinfunction "1_1") (pintype "passive"))
      (node (ref "R32") (pin "1") (pinfunction "1_1") (pintype "passive"))
      (node (ref "R34") (pin "2") (pinfunction "2_2") (pintype "passive"))
      (node (ref "R6") (pin "P$2") (pinfunction "2_P$2") (pintype "passive"))
      (node (ref "R8") (pin "2") (pinfunction "2_2") (pintype "passive"))
      (node (ref "RB3") (pin "1") (pinfunction "1_1") (pintype "passive"))
      (node (ref "ROM-58C256") (pin "27") (pinfunction "~{WE}_27") (pintype "input"))
      (node (ref "ROM-58C256") (pin "28") (pinfunction "VCC_28") (pintype "power_in"))
      (node (ref "SL4") (pin "10") (pinfunction "10_10") (pintype "passive"))
      (node (ref "U$1") (pin "1") (pinfunction "1_1") (pintype "passive"))
      (node (ref "U$2") (pin "VBUS") (pinfunction "VCC_VBUS") (pintype "power_in"))
      (node (ref "U$3") (pin "2") (pinfunction "V+_2") (pintype "power_in"))
    )
    (net (code "88") (name "unconnected-(DECODERA-Y0-Pad15)") (class "Default")
      (node (ref "DECODER") (pin "15") (pinfunction "Y0_15") (pintype "output"))
    )
    (net (code "89") (name "unconnected-(DECODERA-Y3-Pad12)") (class "Default")
      (node (ref "DECODER") (pin "12") (pinfunction "Y3_12") (pintype "output"))
    )
    (net (code "90") (name "unconnected-(DECODERA-Y4-Pad11)") (class "Default")
      (node (ref "DECODER") (pin "11") (pinfunction "Y4_11") (pintype "output"))
    )
    (net (code "91") (name "unconnected-(DECODERA-Y7-Pad7)") (class "Default")
      (node (ref "DECODER") (pin "7") (pinfunction "Y7_7") (pintype "output"))
    )
  )
)
